# PGA_Block.net
KiCad netlist of a schematic drawn in Altium Designer
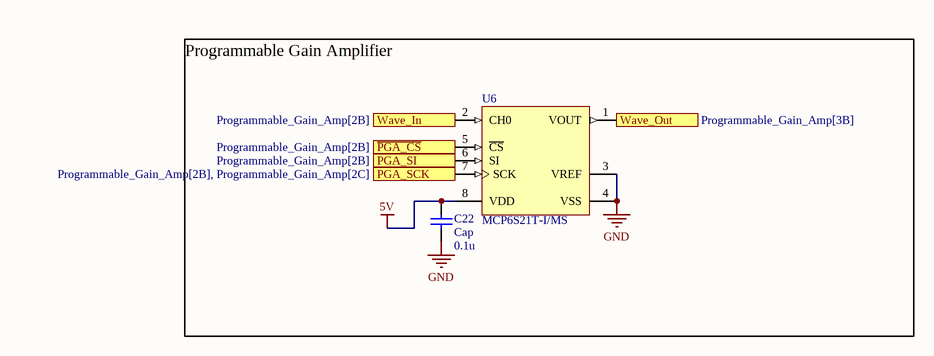
[diagram p0: PGA_Block.SchDoc]

(export (version "E")
  (design (tool "Eeschema 10.0.6"))
  (components
    (comp (ref "C22")
      (value "Cap")
      (footprint "0402_Res")
      (description "Capacitor")
      (fields (field (name "ALTIUM_VALUE") "0.1u") (field (name "PUBLISHER") "Altium Limited"))
      (libsource (lib "Miscellaneous Devices") (part "Cap"))
    )
    (comp (ref "U6")
      (value "MCP6S21T-I/MS")
      (footprint "MSOP-MS8_N")
      (libsource (lib "Altium Content Vault") (part "AMP-VGA-MCP6S21-IL8"))
    )
  )
  (nets
    (net (code "1") (name "/PGA_SCK") (class "Default")
      (node (ref "U6") (pin "7") (pinfunction "SCK_7") (pintype "input"))
    )
    (net (code "2") (name "/PGA_SI") (class "Default")
      (node (ref "U6") (pin "6") (pinfunction "SI_6") (pintype "input"))
    )
    (net (code "3") (name "/Wave_In") (class "Default")
      (node (ref "U6") (pin "2") (pinfunction "CH0_2") (pintype "input"))
    )
    (net (code "4") (name "/Wave_Out") (class "Default")
      (node (ref "U6") (pin "1") (pinfunction "VOUT_1") (pintype "output"))
    )
    (net (code "5") (name "/~{PGA_CS}") (class "Default")
      (node (ref "U6") (pin "5") (pinfunction "~{CS}_5") (pintype "input"))
    )
    (net (code "6") (name "5V") (class "Default")
      (node (ref "C22") (pin "2") (pinfunction "2_2") (pintype "passive"))
      (node (ref "U6") (pin "8") (pinfunction "VDD_8") (pintype "power_in"))
    )
    (net (code "7") (name "GND") (class "Default")
      (node (ref "C22") (pin "1") (pinfunction "1_1") (pintype "passive"))
      (node (ref "U6") (pin "3") (pinfunction "VREF_3") (pintype "power_in"))
      (node (ref "U6") (pin "4") (pinfunction "VSS_4") (pintype "power_in"))
    )
  )
)
